# HumFlex3_upper.net
KiCad netlist of a schematic drawn in Altium Designer
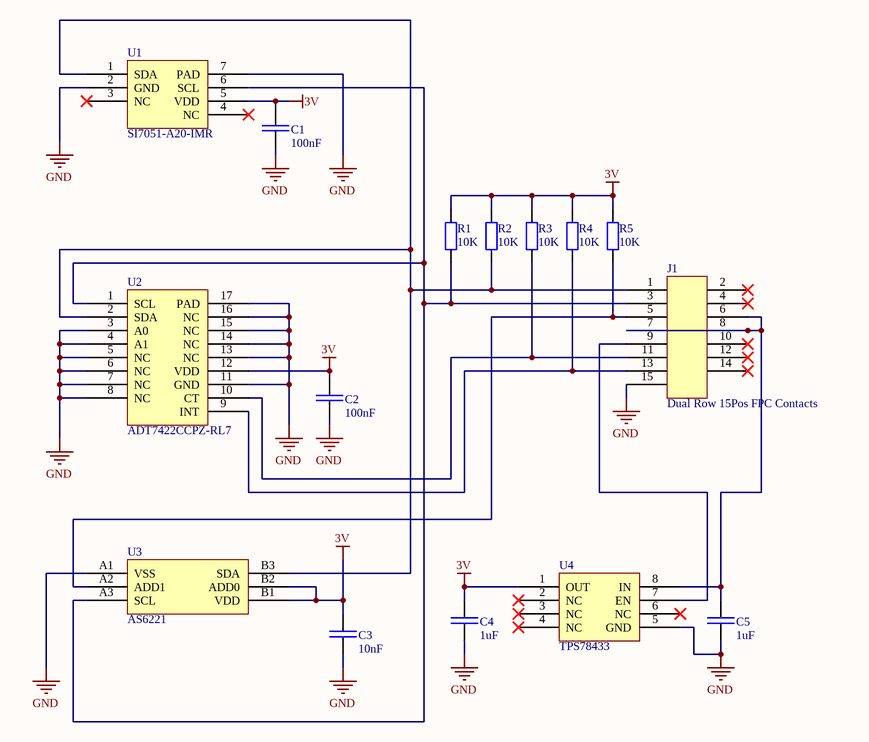
[diagram p0: HumFlex3_upper.SchDoc]

(export (version "E")
  (design (tool "Eeschema 10.0.6"))
  (components
    (comp (ref "C1")
      (value "100nF")
      (footprint "CAP_SM0603_YAGEOCC2_N")
      (description "CAP 100nF SM0603 X7R 50V YAGEO CC2")
      (fields
        (field (name "MANUFACTURER") "Yageo")
        (field (name "MANUFACTURER PART NUMBER") "CC0603KRX7R9BB104")
      )
      (libsource (lib "symbols") (part "CC0603KRX7R9BB104"))
    )
    (comp (ref "C2")
      (value "100nF")
      (footprint "CAP_SM0603_YAGEOCC2_N")
      (description "CAP 100nF SM0603 X7R 50V YAGEO CC2")
      (fields
        (field (name "MANUFACTURER") "Yageo")
        (field (name "MANUFACTURER PART NUMBER") "CC0603KRX7R9BB104")
      )
      (libsource (lib "symbols") (part "CC0603KRX7R9BB104"))
    )
    (comp (ref "C3")
      (value "10nF")
      (footprint "CAP_SM0402_YAGEOCC2_N")
      (description "CAP 10nF SM0402 X7R 50V YAGEO CC2")
      (fields
        (field (name "MANUFACTURER") "Yageo")
        (field (name "MANUFACTURER PART NUMBER") "CC0603KRX7R9BB103")
      )
      (libsource (lib "symbols") (part "CC0402KRX7R9BB103"))
    )
    (comp (ref "C4")
      (value "1uF")
      (footprint "CAP_SM0805_YAGEOCC2_N")
      (description "CAP 1uF SM0805 X7R 25V YAGEO CC2")
      (fields
        (field (name "MANUFACTURER") "Yageo")
        (field (name "MANUFACTURER PART NUMBER") "CC0805KKX7R8BB105")
      )
      (libsource (lib "symbols") (part "CC0805KKX7R8BB105"))
    )
    (comp (ref "C5")
      (value "1uF")
      (footprint "CAP_SM0805_YAGEOCC2_N")
      (description "CAP 1uF SM0805 X7R 25V YAGEO CC2")
      (fields
        (field (name "MANUFACTURER") "Yageo")
        (field (name "MANUFACTURER PART NUMBER") "CC0805KKX7R8BB105")
      )
      (libsource (lib "symbols") (part "CC0805KKX7R8BB105"))
    )
    (comp (ref "J1")
      (value "Dual Row 15Pos FPC Contacts")
      (footprint "AYF331535_FPC")
      (libsource (lib "symbols") (part "FPC_Contacts_15_DualRow"))
    )
    (comp (ref "R1")
      (value "10K")
      (footprint "RES_SM0603_YAGEORC_N")
      (description "RES 10K SM0603 YAGEO RC_L")
      (fields
        (field (name "MANUFACTURER") "Yageo")
        (field (name "MANUFACTURER PART NUMBER") "RC0603FR-0710KL")
      )
      (libsource (lib "symbols") (part "RC0603FR-0710KL"))
    )
    (comp (ref "R2")
      (value "10K")
      (footprint "RES_SM0603_YAGEORC_N")
      (description "RES 10K SM0603 YAGEO RC_L")
      (fields
        (field (name "MANUFACTURER") "Yageo")
        (field (name "MANUFACTURER PART NUMBER") "RC0603FR-0710KL")
      )
      (libsource (lib "symbols") (part "RC0603FR-0710KL"))
    )
    (comp (ref "R3")
      (value "10K")
      (footprint "RES_SM0603_YAGEORC_N")
      (description "RES 10K SM0603 YAGEO RC_L")
      (fields
        (field (name "MANUFACTURER") "Yageo")
        (field (name "MANUFACTURER PART NUMBER") "RC0603FR-0710KL")
      )
      (libsource (lib "symbols") (part "RC0603FR-0710KL"))
    )
    (comp (ref "R4")
      (value "10K")
      (footprint "RES_SM0603_YAGEORC_N")
      (description "RES 10K SM0603 YAGEO RC_L")
      (fields
        (field (name "MANUFACTURER") "Yageo")
        (field (name "MANUFACTURER PART NUMBER") "RC0603FR-0710KL")
      )
      (libsource (lib "symbols") (part "RC0603FR-0710KL"))
    )
    (comp (ref "R5")
      (value "10K")
      (footprint "RES_SM0603_YAGEORC_N")
      (description "RES 10K SM0603 YAGEO RC_L")
      (fields
        (field (name "MANUFACTURER") "Yageo")
        (field (name "MANUFACTURER PART NUMBER") "RC0603FR-0710KL")
      )
      (libsource (lib "symbols") (part "RC0603FR-0710KL"))
    )
    (comp (ref "U1")
      (value "SI7051-A20-IMR")
      (footprint "SI7050/1/2/3/4/5")
      (description "Si7051-A20 Temperature Sensor ±0.1°C maximum accuracy, Digital I2C, -40°C ~ 125°C 14b 6-DFN (3x3)")
      (libsource (lib "symbols") (part "SI7051-A20-IMR"))
    )
    (comp (ref "U2")
      (value "ADT7422CCPZ-RL7")
      (footprint "ADT7422_QFN")
      (libsource (lib "symbols") (part "ADT7422CCPZ-RL7"))
    )
    (comp (ref "U3")
      (value "AS6221")
      (footprint "AS6221_BGA")
      (description "AS6221 Temperature Sensor Digital -40°C ~ 125°C 16b 6-WLCSP (1.5x1.03)")
      (libsource (lib "symbols") (part "AS6221-AWLT-S"))
    )
    (comp (ref "U4")
      (value "TPS78433")
      (footprint "TPS784xxxQDRBRQ1_SON")
      (libsource (lib "symbols") (part "TPS78433QWDRBRQ1"))
    )
  )
  (nets
    (net (code "1") (name "3V") (class "Default")
      (node (ref "C1") (pin "2") (pintype "passive"))
      (node (ref "C2") (pin "2") (pintype "passive"))
      (node (ref "C3") (pin "1") (pintype "passive"))
      (node (ref "C4") (pin "2") (pintype "passive"))
      (node (ref "R1") (pin "2") (pintype "passive"))
      (node (ref "R2") (pin "2") (pintype "passive"))
      (node (ref "R3") (pin "2") (pintype "passive"))
      (node (ref "R4") (pin "2") (pintype "passive"))
      (node (ref "R5") (pin "2") (pintype "passive"))
      (node (ref "U1") (pin "5") (pinfunction "VDD_5") (pintype "passive"))
      (node (ref "U2") (pin "12") (pinfunction "VDD_12") (pintype "passive"))
      (node (ref "U3") (pin "B1") (pinfunction "VDD_B1") (pintype "passive"))
      (node (ref "U3") (pin "B2") (pinfunction "ADD0_B2") (pintype "passive"))
      (node (ref "U4") (pin "1") (pinfunction "OUT_1") (pintype "passive"))
    )
    (net (code "2") (name "GND") (class "Default")
      (node (ref "C1") (pin "1") (pintype "passive"))
      (node (ref "C2") (pin "1") (pintype "passive"))
      (node (ref "C3") (pin "2") (pintype "passive"))
      (node (ref "C4") (pin "1") (pintype "passive"))
      (node (ref "C5") (pin "1") (pintype "passive"))
      (node (ref "J1") (pin "15") (pintype "passive"))
      (node (ref "U1") (pin "2") (pinfunction "GND_2") (pintype "passive"))
      (node (ref "U1") (pin "7") (pinfunction "PAD_7") (pintype "passive"))
      (node (ref "U2") (pin "11") (pinfunction "GND_11") (pintype "passive"))
      (node (ref "U2") (pin "13") (pinfunction "NC_13") (pintype "passive"))
      (node (ref "U2") (pin "14") (pinfunction "NC_14") (pintype "passive"))
      (node (ref "U2") (pin "15") (pinfunction "NC_15") (pintype "passive"))
      (node (ref "U2") (pin "16") (pinfunction "NC_16") (pintype "passive"))
      (node (ref "U2") (pin "17") (pinfunction "PAD_17") (pintype "passive"))
      (node (ref "U2") (pin "3") (pinfunction "A0_3") (pintype "passive"))
      (node (ref "U2") (pin "4") (pinfunction "A1_4") (pintype "passive"))
      (node (ref "U2") (pin "5") (pinfunction "NC_5") (pintype "passive"))
      (node (ref "U2") (pin "6") (pinfunction "NC_6") (pintype "passive"))
      (node (ref "U2") (pin "7") (pinfunction "NC_7") (pintype "passive"))
      (node (ref "U2") (pin "8") (pinfunction "NC_8") (pintype "passive"))
      (node (ref "U3") (pin "A1") (pinfunction "VSS_A1") (pintype "passive"))
      (node (ref "U4") (pin "5") (pinfunction "GND_5") (pintype "passive"))
    )
    (net (code "3") (name "Net-(U1-SCL)") (class "Default")
      (node (ref "J1") (pin "3") (pintype "passive"))
      (node (ref "R1") (pin "1") (pintype "passive"))
      (node (ref "U1") (pin "6") (pinfunction "SCL_6") (pintype "passive"))
      (node (ref "U2") (pin "1") (pinfunction "SCL_1") (pintype "passive"))
      (node (ref "U3") (pin "A3") (pinfunction "SCL_A3") (pintype "passive"))
    )
    (net (code "4") (name "Net-(U1-SDA)") (class "Default")
      (node (ref "J1") (pin "1") (pintype "passive"))
      (node (ref "R2") (pin "1") (pintype "passive"))
      (node (ref "U1") (pin "1") (pinfunction "SDA_1") (pintype "passive"))
      (node (ref "U2") (pin "2") (pinfunction "SDA_2") (pintype "passive"))
      (node (ref "U3") (pin "B3") (pinfunction "SDA_B3") (pintype "passive"))
    )
    (net (code "5") (name "Net-(U2-CT)") (class "Default")
      (node (ref "J1") (pin "11") (pintype "passive"))
      (node (ref "R3") (pin "1") (pintype "passive"))
      (node (ref "U2") (pin "10") (pinfunction "CT_10") (pintype "passive"))
    )
    (net (code "6") (name "Net-(U2-INT)") (class "Default")
      (node (ref "J1") (pin "13") (pintype "passive"))
      (node (ref "R4") (pin "1") (pintype "passive"))
      (node (ref "U2") (pin "9") (pinfunction "INT_9") (pintype "passive"))
    )
    (net (code "7") (name "Net-(U3-ADD1)") (class "Default")
      (node (ref "J1") (pin "5") (pintype "passive"))
      (node (ref "R5") (pin "1") (pintype "passive"))
      (node (ref "U3") (pin "A2") (pinfunction "ADD1_A2") (pintype "passive"))
    )
    (net (code "8") (name "Net-(U4-EN)") (class "Default")
      (node (ref "J1") (pin "9") (pintype "passive"))
      (node (ref "U4") (pin "7") (pinfunction "EN_7") (pintype "passive"))
    )
    (net (code "9") (name "Net-(U4-IN)") (class "Default")
      (node (ref "C5") (pin "2") (pintype "passive"))
      (node (ref "J1") (pin "6") (pintype "passive"))
      (node (ref "J1") (pin "7") (pintype "passive"))
      (node (ref "J1") (pin "8") (pintype "passive"))
      (node (ref "U4") (pin "8") (pinfunction "IN_8") (pintype "passive"))
    )
    (net (code "10") (name "unconnected-(J1-Pad2)") (class "Default")
      (node (ref "J1") (pin "2") (pintype "passive+no_connect"))
    )
    (net (code "11") (name "unconnected-(J1-Pad4)") (class "Default")
      (node (ref "J1") (pin "4") (pintype "passive+no_connect"))
    )
    (net (code "12") (name "unconnected-(J1-Pad10)") (class "Default")
      (node (ref "J1") (pin "10") (pintype "passive+no_connect"))
    )
    (net (code "13") (name "unconnected-(J1-Pad12)") (class "Default")
      (node (ref "J1") (pin "12") (pintype "passive+no_connect"))
    )
    (net (code "14") (name "unconnected-(J1-Pad14)") (class "Default")
      (node (ref "J1") (pin "14") (pintype "passive+no_connect"))
    )
    (net (code "15") (name "unconnected-(U1-NC-Pad3)") (class "Default")
      (node (ref "U1") (pin "3") (pinfunction "NC_3") (pintype "passive+no_connect"))
    )
    (net (code "16") (name "unconnected-(U1-NC-Pad4)") (class "Default")
      (node (ref "U1") (pin "4") (pinfunction "NC_4") (pintype "passive+no_connect"))
    )
    (net (code "17") (name "unconnected-(U4-NC-Pad2)") (class "Default")
      (node (ref "U4") (pin "2") (pinfunction "NC_2") (pintype "passive+no_connect"))
    )
    (net (code "18") (name "unconnected-(U4-NC-Pad3)") (class "Default")
      (node (ref "U4") (pin "3") (pinfunction "NC_3") (pintype "passive+no_connect"))
    )
    (net (code "19") (name "unconnected-(U4-NC-Pad4)") (class "Default")
      (node (ref "U4") (pin "4") (pinfunction "NC_4") (pintype "passive+no_connect"))
    )
    (net (code "20") (name "unconnected-(U4-NC-Pad6)") (class "Default")
      (node (ref "U4") (pin "6") (pinfunction "NC_6") (pintype "passive+no_connect"))
    )
  )
)
